# epm_control.net
KiCad netlist of a schematic drawn in Altium Designer
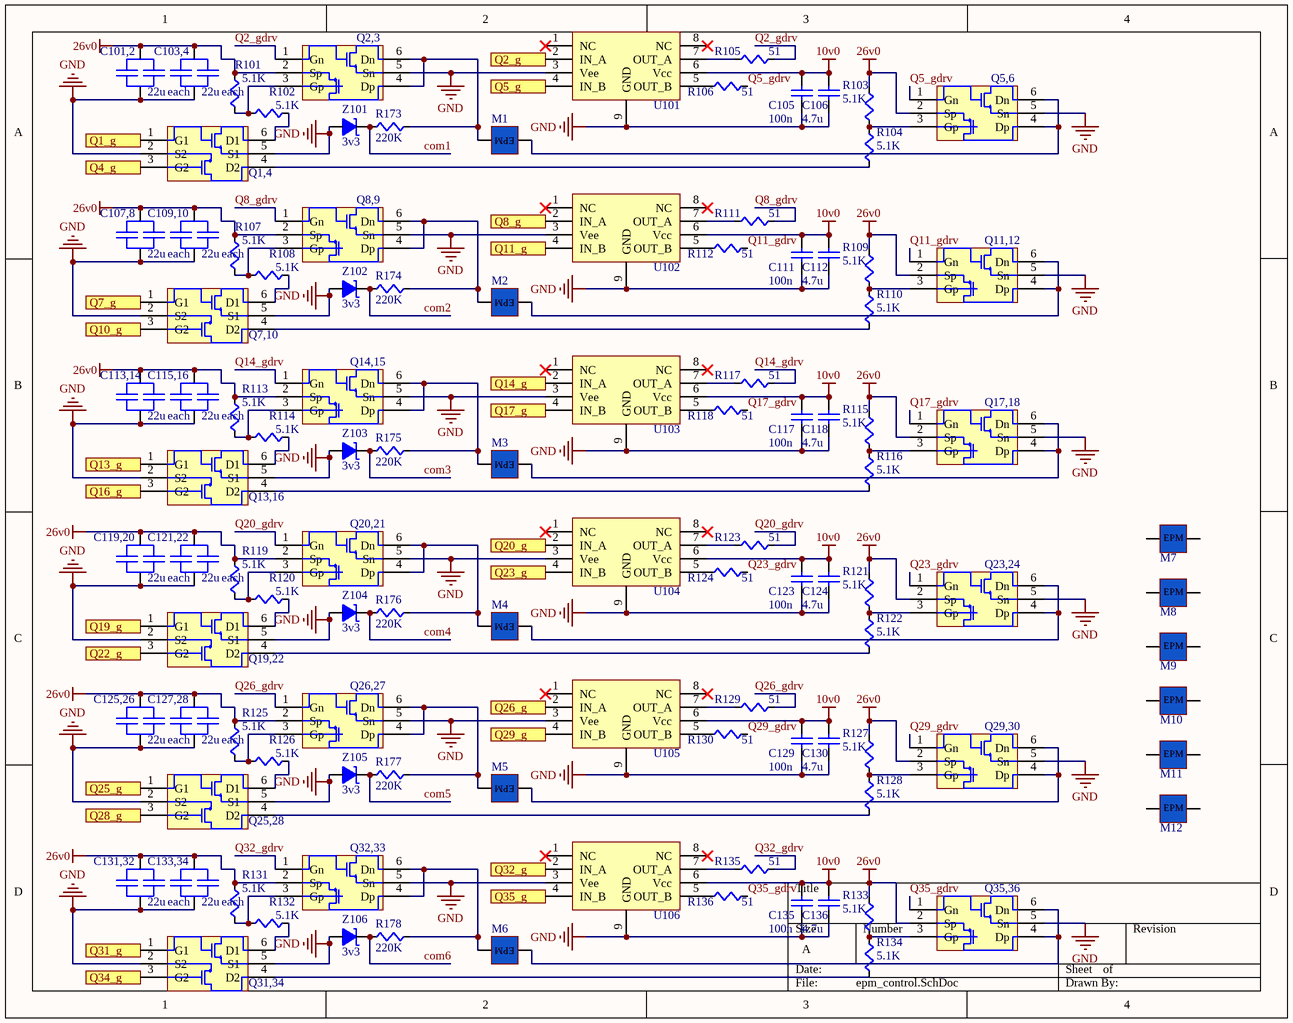
[diagram p0: epm_control.SchDoc]

(export (version "E")
  (design (tool "Eeschema 10.0.6"))
  (components
    (comp (ref "C101,2")
      (value "22u")
      (footprint "dicap_smd_1206")
      (fields (field (name "Comment") "Dicap"))
      (libsource (lib "Components") (part "Dicap"))
    )
    (comp (ref "C103,4")
      (value "22u")
      (footprint "dicap_smd_1206")
      (fields (field (name "Comment") "Dicap"))
      (libsource (lib "Components") (part "Dicap"))
    )
    (comp (ref "C105")
      (value "100n")
      (footprint "SMD0603_cap")
      (description "Ceramic Chip Capacitor")
      (fields (field (name "Comment") "Cap"))
      (libsource (lib "Components") (part "Capacitor Ceramic"))
    )
    (comp (ref "C106")
      (value "4.7u")
      (footprint "SMD0603_cap")
      (description "Ceramic Chip Capacitor")
      (fields (field (name "Comment") "Cap"))
      (libsource (lib "Components") (part "Capacitor Ceramic"))
    )
    (comp (ref "C107,8")
      (value "22u")
      (footprint "dicap_smd_1206")
      (fields (field (name "Comment") "Dicap"))
      (libsource (lib "Components") (part "Dicap"))
    )
    (comp (ref "C109,10")
      (value "22u")
      (footprint "dicap_smd_1206")
      (fields (field (name "Comment") "Dicap"))
      (libsource (lib "Components") (part "Dicap"))
    )
    (comp (ref "C111")
      (value "100n")
      (footprint "SMD0603_cap")
      (description "Ceramic Chip Capacitor")
      (fields (field (name "Comment") "Cap"))
      (libsource (lib "Components") (part "Capacitor Ceramic"))
    )
    (comp (ref "C112")
      (value "4.7u")
      (footprint "SMD0603_cap")
      (description "Ceramic Chip Capacitor")
      (fields (field (name "Comment") "Cap"))
      (libsource (lib "Components") (part "Capacitor Ceramic"))
    )
    (comp (ref "C113,14")
      (value "22u")
      (footprint "dicap_smd_1206")
      (fields (field (name "Comment") "Dicap"))
      (libsource (lib "Components") (part "Dicap"))
    )
    (comp (ref "C115,16")
      (value "22u")
      (footprint "dicap_smd_1206")
      (fields (field (name "Comment") "Dicap"))
      (libsource (lib "Components") (part "Dicap"))
    )
    (comp (ref "C117")
      (value "100n")
      (footprint "SMD0603_cap")
      (description "Ceramic Chip Capacitor")
      (fields (field (name "Comment") "Cap"))
      (libsource (lib "Components") (part "Capacitor Ceramic"))
    )
    (comp (ref "C118")
      (value "4.7u")
      (footprint "SMD0603_cap")
      (description "Ceramic Chip Capacitor")
      (fields (field (name "Comment") "Cap"))
      (libsource (lib "Components") (part "Capacitor Ceramic"))
    )
    (comp (ref "C119,20")
      (value "22u")
      (footprint "dicap_smd_1206")
      (fields (field (name "Comment") "Dicap"))
      (libsource (lib "Components") (part "Dicap"))
    )
    (comp (ref "C121,22")
      (value "22u")
      (footprint "dicap_smd_1206")
      (fields (field (name "Comment") "Dicap"))
      (libsource (lib "Components") (part "Dicap"))
    )
    (comp (ref "C123")
      (value "100n")
      (footprint "SMD0603_cap")
      (description "Ceramic Chip Capacitor")
      (fields (field (name "Comment") "Cap"))
      (libsource (lib "Components") (part "Capacitor Ceramic"))
    )
    (comp (ref "C124")
      (value "4.7u")
      (footprint "SMD0603_cap")
      (description "Ceramic Chip Capacitor")
      (fields (field (name "Comment") "Cap"))
      (libsource (lib "Components") (part "Capacitor Ceramic"))
    )
    (comp (ref "C125,26")
      (value "22u")
      (footprint "dicap_smd_1206")
      (fields (field (name "Comment") "Dicap"))
      (libsource (lib "Components") (part "Dicap"))
    )
    (comp (ref "C127,28")
      (value "22u")
      (footprint "dicap_smd_1206")
      (fields (field (name "Comment") "Dicap"))
      (libsource (lib "Components") (part "Dicap"))
    )
    (comp (ref "C129")
      (value "100n")
      (footprint "SMD0603_cap")
      (description "Ceramic Chip Capacitor")
      (fields (field (name "Comment") "Cap"))
      (libsource (lib "Components") (part "Capacitor Ceramic"))
    )
    (comp (ref "C130")
      (value "4.7u")
      (footprint "SMD0603_cap")
      (description "Ceramic Chip Capacitor")
      (fields (field (name "Comment") "Cap"))
      (libsource (lib "Components") (part "Capacitor Ceramic"))
    )
    (comp (ref "C131,32")
      (value "22u")
      (footprint "dicap_smd_1206")
      (fields (field (name "Comment") "Dicap"))
      (libsource (lib "Components") (part "Dicap"))
    )
    (comp (ref "C133,34")
      (value "22u")
      (footprint "dicap_smd_1206")
      (fields (field (name "Comment") "Dicap"))
      (libsource (lib "Components") (part "Dicap"))
    )
    (comp (ref "C135")
      (value "100n")
      (footprint "SMD0603_cap")
      (description "Ceramic Chip Capacitor")
      (fields (field (name "Comment") "Cap"))
      (libsource (lib "Components") (part "Capacitor Ceramic"))
    )
    (comp (ref "C136")
      (value "4.7u")
      (footprint "SMD0603_cap")
      (description "Ceramic Chip Capacitor")
      (fields (field (name "Comment") "Cap"))
      (libsource (lib "Components") (part "Capacitor Ceramic"))
    )
    (comp (ref "M1") (value "EPM") (footprint "40awg_epm") (libsource (lib "Components") (part "EPM")))
    (comp (ref "M2") (value "EPM") (footprint "40awg_epm") (libsource (lib "Components") (part "EPM")))
    (comp (ref "M3") (value "EPM") (footprint "40awg_epm") (libsource (lib "Components") (part "EPM")))
    (comp (ref "M4") (value "EPM") (footprint "40awg_epm") (libsource (lib "Components") (part "EPM")))
    (comp (ref "M5") (value "EPM") (footprint "40awg_epm") (libsource (lib "Components") (part "EPM")))
    (comp (ref "M6") (value "EPM") (footprint "40awg_epm") (libsource (lib "Components") (part "EPM")))
    (comp (ref "M7") (value "EPM") (footprint "40awg_epm") (libsource (lib "") (part "EPM_1")))
    (comp (ref "M8") (value "EPM") (footprint "40awg_epm") (libsource (lib "") (part "EPM_1")))
    (comp (ref "M9") (value "EPM") (footprint "40awg_epm") (libsource (lib "") (part "EPM_1")))
    (comp (ref "M10") (value "EPM") (footprint "40awg_epm") (libsource (lib "") (part "EPM_1")))
    (comp (ref "M11") (value "EPM") (footprint "40awg_epm") (libsource (lib "") (part "EPM_1")))
    (comp (ref "M12") (value "EPM") (footprint "40awg_epm") (libsource (lib "") (part "EPM_1")))
    (comp (ref "Q1,4") (value "SI3292") (footprint "sot23-6l") (libsource (lib "Components") (part "SI3292")))
    (comp (ref "Q2,3")
      (value "DMG6602")
      (footprint "sot23-6l")
      (libsource (lib "Components") (part "DMG6602"))
    )
    (comp (ref "Q5,6")
      (value "DMG6602")
      (footprint "sot23-6l")
      (libsource (lib "Components") (part "DMG6602"))
    )
    (comp (ref "Q7,10")
      (value "SI3292")
      (footprint "sot23-6l")
      (libsource (lib "Components") (part "SI3292"))
    )
    (comp (ref "Q8,9")
      (value "DMG6602")
      (footprint "sot23-6l")
      (libsource (lib "Components") (part "DMG6602"))
    )
    (comp (ref "Q11,12")
      (value "DMG6602")
      (footprint "sot23-6l")
      (libsource (lib "Components") (part "DMG6602"))
    )
    (comp (ref "Q13,16")
      (value "SI3292")
      (footprint "sot23-6l")
      (libsource (lib "Components") (part "SI3292"))
    )
    (comp (ref "Q14,15")
      (value "DMG6602")
      (footprint "sot23-6l")
      (libsource (lib "Components") (part "DMG6602"))
    )
    (comp (ref "Q17,18")
      (value "DMG6602")
      (footprint "sot23-6l")
      (libsource (lib "Components") (part "DMG6602"))
    )
    (comp (ref "Q19,22")
      (value "SI3292")
      (footprint "sot23-6l")
      (libsource (lib "Components") (part "SI3292"))
    )
    (comp (ref "Q20,21")
      (value "DMG6602")
      (footprint "sot23-6l")
      (libsource (lib "Components") (part "DMG6602"))
    )
    (comp (ref "Q23,24")
      (value "DMG6602")
      (footprint "sot23-6l")
      (libsource (lib "Components") (part "DMG6602"))
    )
    (comp (ref "Q25,28")
      (value "SI3292")
      (footprint "sot23-6l")
      (libsource (lib "Components") (part "SI3292"))
    )
    (comp (ref "Q26,27")
      (value "DMG6602")
      (footprint "sot23-6l")
      (libsource (lib "Components") (part "DMG6602"))
    )
    (comp (ref "Q29,30")
      (value "DMG6602")
      (footprint "sot23-6l")
      (libsource (lib "Components") (part "DMG6602"))
    )
    (comp (ref "Q31,34")
      (value "SI3292")
      (footprint "sot23-6l")
      (libsource (lib "Components") (part "SI3292"))
    )
    (comp (ref "Q32,33")
      (value "DMG6602")
      (footprint "sot23-6l")
      (libsource (lib "Components") (part "DMG6602"))
    )
    (comp (ref "Q35,36")
      (value "DMG6602")
      (footprint "sot23-6l")
      (libsource (lib "Components") (part "DMG6602"))
    )
    (comp (ref "R101")
      (value "5.1K")
      (footprint "SMD0603")
      (description "Resistor")
      (fields (field (name "Comment") "Res"))
      (libsource (lib "Components") (part "Resistor"))
    )
    (comp (ref "R102")
      (value "5.1K")
      (footprint "SMD0603")
      (description "Resistor")
      (fields (field (name "Comment") "Res"))
      (libsource (lib "Components") (part "Resistor"))
    )
    (comp (ref "R103")
      (value "5.1K")
      (footprint "SMD0603")
      (description "Resistor")
      (fields (field (name "Comment") "Res"))
      (libsource (lib "Components") (part "Resistor"))
    )
    (comp (ref "R104")
      (value "5.1K")
      (footprint "SMD0603")
      (description "Resistor")
      (fields (field (name "Comment") "Res"))
      (libsource (lib "Components") (part "Resistor"))
    )
    (comp (ref "R105")
      (value "51")
      (footprint "SMD0603")
      (description "Resistor")
      (fields (field (name "Comment") "Res"))
      (libsource (lib "Components") (part "Resistor"))
    )
    (comp (ref "R106")
      (value "51")
      (footprint "SMD0603")
      (description "Resistor")
      (fields (field (name "Comment") "Res"))
      (libsource (lib "Components") (part "Resistor"))
    )
    (comp (ref "R107")
      (value "5.1K")
      (footprint "SMD0603")
      (description "Resistor")
      (fields (field (name "Comment") "Res"))
      (libsource (lib "Components") (part "Resistor"))
    )
    (comp (ref "R108")
      (value "5.1K")
      (footprint "SMD0603")
      (description "Resistor")
      (fields (field (name "Comment") "Res"))
      (libsource (lib "Components") (part "Resistor"))
    )
    (comp (ref "R109")
      (value "5.1K")
      (footprint "SMD0603")
      (description "Resistor")
      (fields (field (name "Comment") "Res"))
      (libsource (lib "Components") (part "Resistor"))
    )
    (comp (ref "R110")
      (value "5.1K")
      (footprint "SMD0603")
      (description "Resistor")
      (fields (field (name "Comment") "Res"))
      (libsource (lib "Components") (part "Resistor"))
    )
    (comp (ref "R111")
      (value "51")
      (footprint "SMD0603")
      (description "Resistor")
      (fields (field (name "Comment") "Res"))
      (libsource (lib "Components") (part "Resistor"))
    )
    (comp (ref "R112")
      (value "51")
      (footprint "SMD0603")
      (description "Resistor")
      (fields (field (name "Comment") "Res"))
      (libsource (lib "Components") (part "Resistor"))
    )
    (comp (ref "R113")
      (value "5.1K")
      (footprint "SMD0603")
      (description "Resistor")
      (fields (field (name "Comment") "Res"))
      (libsource (lib "Components") (part "Resistor"))
    )
    (comp (ref "R114")
      (value "5.1K")
      (footprint "SMD0603")
      (description "Resistor")
      (fields (field (name "Comment") "Res"))
      (libsource (lib "Components") (part "Resistor"))
    )
    (comp (ref "R115")
      (value "5.1K")
      (footprint "SMD0603")
      (description "Resistor")
      (fields (field (name "Comment") "Res"))
      (libsource (lib "Components") (part "Resistor"))
    )
    (comp (ref "R116")
      (value "5.1K")
      (footprint "SMD0603")
      (description "Resistor")
      (fields (field (name "Comment") "Res"))
      (libsource (lib "Components") (part "Resistor"))
    )
    (comp (ref "R117")
      (value "51")
      (footprint "SMD0603")
      (description "Resistor")
      (fields (field (name "Comment") "Res"))
      (libsource (lib "Components") (part "Resistor"))
    )
    (comp (ref "R118")
      (value "51")
      (footprint "SMD0603")
      (description "Resistor")
      (fields (field (name "Comment") "Res"))
      (libsource (lib "Components") (part "Resistor"))
    )
    (comp (ref "R119")
      (value "5.1K")
      (footprint "SMD0603")
      (description "Resistor")
      (fields (field (name "Comment") "Res"))
      (libsource (lib "Components") (part "Resistor"))
    )
    (comp (ref "R120")
      (value "5.1K")
      (footprint "SMD0603")
      (description "Resistor")
      (fields (field (name "Comment") "Res"))
      (libsource (lib "Components") (part "Resistor"))
    )
    (comp (ref "R121")
      (value "5.1K")
      (footprint "SMD0603")
      (description "Resistor")
      (fields (field (name "Comment") "Res"))
      (libsource (lib "Components") (part "Resistor"))
    )
    (comp (ref "R122")
      (value "5.1K")
      (footprint "SMD0603")
      (description "Resistor")
      (fields (field (name "Comment") "Res"))
      (libsource (lib "Components") (part "Resistor"))
    )
    (comp (ref "R123")
      (value "51")
      (footprint "SMD0603")
      (description "Resistor")
      (fields (field (name "Comment") "Res"))
      (libsource (lib "Components") (part "Resistor"))
    )
    (comp (ref "R124")
      (value "51")
      (footprint "SMD0603")
      (description "Resistor")
      (fields (field (name "Comment") "Res"))
      (libsource (lib "Components") (part "Resistor"))
    )
    (comp (ref "R125")
      (value "5.1K")
      (footprint "SMD0603")
      (description "Resistor")
      (fields (field (name "Comment") "Res"))
      (libsource (lib "Components") (part "Resistor"))
    )
    (comp (ref "R126")
      (value "5.1K")
      (footprint "SMD0603")
      (description "Resistor")
      (fields (field (name "Comment") "Res"))
      (libsource (lib "Components") (part "Resistor"))
    )
    (comp (ref "R127")
      (value "5.1K")
      (footprint "SMD0603")
      (description "Resistor")
      (fields (field (name "Comment") "Res"))
      (libsource (lib "Components") (part "Resistor"))
    )
    (comp (ref "R128")
      (value "5.1K")
      (footprint "SMD0603")
      (description "Resistor")
      (fields (field (name "Comment") "Res"))
      (libsource (lib "Components") (part "Resistor"))
    )
    (comp (ref "R129")
      (value "51")
      (footprint "SMD0603")
      (description "Resistor")
      (fields (field (name "Comment") "Res"))
      (libsource (lib "Components") (part "Resistor"))
    )
    (comp (ref "R130")
      (value "51")
      (footprint "SMD0603")
      (description "Resistor")
      (fields (field (name "Comment") "Res"))
      (libsource (lib "Components") (part "Resistor"))
    )
    (comp (ref "R131")
      (value "5.1K")
      (footprint "SMD0603")
      (description "Resistor")
      (fields (field (name "Comment") "Res"))
      (libsource (lib "Components") (part "Resistor"))
    )
    (comp (ref "R132")
      (value "5.1K")
      (footprint "SMD0603")
      (description "Resistor")
      (fields (field (name "Comment") "Res"))
      (libsource (lib "Components") (part "Resistor"))
    )
    (comp (ref "R133")
      (value "5.1K")
      (footprint "SMD0603")
      (description "Resistor")
      (fields (field (name "Comment") "Res"))
      (libsource (lib "Components") (part "Resistor"))
    )
    (comp (ref "R134")
      (value "5.1K")
      (footprint "SMD0603")
      (description "Resistor")
      (fields (field (name "Comment") "Res"))
      (libsource (lib "Components") (part "Resistor"))
    )
    (comp (ref "R135")
      (value "51")
      (footprint "SMD0603")
      (description "Resistor")
      (fields (field (name "Comment") "Res"))
      (libsource (lib "Components") (part "Resistor"))
    )
    (comp (ref "R136")
      (value "51")
      (footprint "SMD0603")
      (description "Resistor")
      (fields (field (name "Comment") "Res"))
      (libsource (lib "Components") (part "Resistor"))
    )
    (comp (ref "R173")
      (value "220K")
      (footprint "SMD0603")
      (description "Resistor")
      (fields (field (name "Comment") "Res"))
      (libsource (lib "Components") (part "Resistor"))
    )
    (comp (ref "R174")
      (value "220K")
      (footprint "SMD0603")
      (description "Resistor")
      (fields (field (name "Comment") "Res"))
      (libsource (lib "Components") (part "Resistor"))
    )
    (comp (ref "R175")
      (value "220K")
      (footprint "SMD0603")
      (description "Resistor")
      (fields (field (name "Comment") "Res"))
      (libsource (lib "Components") (part "Resistor"))
    )
    (comp (ref "R176")
      (value "220K")
      (footprint "SMD0603")
      (description "Resistor")
      (fields (field (name "Comment") "Res"))
      (libsource (lib "Components") (part "Resistor"))
    )
    (comp (ref "R177")
      (value "220K")
      (footprint "SMD0603")
      (description "Resistor")
      (fields (field (name "Comment") "Res"))
      (libsource (lib "Components") (part "Resistor"))
    )
    (comp (ref "R178")
      (value "220K")
      (footprint "SMD0603")
      (description "Resistor")
      (fields (field (name "Comment") "Res"))
      (libsource (lib "Components") (part "Resistor"))
    )
    (comp (ref "U101")
      (value "LM5111-1")
      (footprint "tssop-8")
      (libsource (lib "Components") (part "LM5111-1"))
    )
    (comp (ref "U102")
      (value "LM5111-1")
      (footprint "tssop-8")
      (libsource (lib "Components") (part "LM5111-1"))
    )
    (comp (ref "U103")
      (value "LM5111-1")
      (footprint "tssop-8")
      (libsource (lib "Components") (part "LM5111-1"))
    )
    (comp (ref "U104")
      (value "LM5111-1")
      (footprint "tssop-8")
      (libsource (lib "Components") (part "LM5111-1"))
    )
    (comp (ref "U105")
      (value "LM5111-1")
      (footprint "tssop-8")
      (libsource (lib "Components") (part "LM5111-1"))
    )
    (comp (ref "U106")
      (value "LM5111-1")
      (footprint "tssop-8")
      (libsource (lib "Components") (part "LM5111-1"))
    )
    (comp (ref "Z101")
      (value "3v3")
      (footprint "SOD-323F")
      (fields (field (name "Comment") "Zener"))
      (libsource (lib "Components") (part "Zener"))
    )
    (comp (ref "Z102")
      (value "3v3")
      (footprint "SOD-323F")
      (fields (field (name "Comment") "Zener"))
      (libsource (lib "Components") (part "Zener"))
    )
    (comp (ref "Z103")
      (value "3v3")
      (footprint "SOD-323F")
      (fields (field (name "Comment") "Zener"))
      (libsource (lib "Components") (part "Zener"))
    )
    (comp (ref "Z104")
      (value "3v3")
      (footprint "SOD-323F")
      (fields (field (name "Comment") "Zener"))
      (libsource (lib "Components") (part "Zener"))
    )
    (comp (ref "Z105")
      (value "3v3")
      (footprint "SOD-323F")
      (fields (field (name "Comment") "Zener"))
      (libsource (lib "Components") (part "Zener"))
    )
    (comp (ref "Z106")
      (value "3v3")
      (footprint "SOD-323F")
      (fields (field (name "Comment") "Zener"))
      (libsource (lib "Components") (part "Zener"))
    )
  )
  (nets
    (net (code "1") (name "/Q1_g") (class "Default")
      (node (ref "Q1,4") (pin "1") (pinfunction "G1_1") (pintype "passive"))
    )
    (net (code "2") (name "/Q2_g") (class "Default")
      (node (ref "U101") (pin "2") (pinfunction "IN_A_2") (pintype "passive"))
    )
    (net (code "3") (name "/Q2_gdrv") (class "Default")
      (node (ref "Q2,3") (pin "1") (pinfunction "Gn_1") (pintype "passive"))
      (node (ref "R105") (pin "1") (pinfunction "1_1") (pintype "passive"))
    )
    (net (code "4") (name "/Q4_g") (class "Default")
      (node (ref "Q1,4") (pin "3") (pinfunction "G2_3") (pintype "passive"))
    )
    (net (code "5") (name "/Q5_g") (class "Default")
      (node (ref "U101") (pin "4") (pinfunction "IN_B_4") (pintype "passive"))
    )
    (net (code "6") (name "/Q5_gdrv") (class "Default")
      (node (ref "Q5,6") (pin "1") (pinfunction "Gn_1") (pintype "passive"))
      (node (ref "R106") (pin "1") (pinfunction "1_1") (pintype "passive"))
    )
    (net (code "7") (name "/Q7_g") (class "Default")
      (node (ref "Q7,10") (pin "1") (pinfunction "G1_1") (pintype "passive"))
    )
    (net (code "8") (name "/Q8_g") (class "Default")
      (node (ref "U102") (pin "2") (pinfunction "IN_A_2") (pintype "passive"))
    )
    (net (code "9") (name "/Q8_gdrv") (class "Default")
      (node (ref "Q8,9") (pin "1") (pinfunction "Gn_1") (pintype "passive"))
      (node (ref "R111") (pin "1") (pinfunction "1_1") (pintype "passive"))
    )
    (net (code "10") (name "/Q10_g") (class "Default")
      (node (ref "Q7,10") (pin "3") (pinfunction "G2_3") (pintype "passive"))
    )
    (net (code "11") (name "/Q11_g") (class "Default")
      (node (ref "U102") (pin "4") (pinfunction "IN_B_4") (pintype "passive"))
    )
    (net (code "12") (name "/Q11_gdrv") (class "Default")
      (node (ref "Q11,12") (pin "1") (pinfunction "Gn_1") (pintype "passive"))
      (node (ref "R112") (pin "1") (pinfunction "1_1") (pintype "passive"))
    )
    (net (code "13") (name "/Q13_g") (class "Default")
      (node (ref "Q13,16") (pin "1") (pinfunction "G1_1") (pintype "passive"))
    )
    (net (code "14") (name "/Q14_g") (class "Default")
      (node (ref "U103") (pin "2") (pinfunction "IN_A_2") (pintype "passive"))
    )
    (net (code "15") (name "/Q14_gdrv") (class "Default")
      (node (ref "Q14,15") (pin "1") (pinfunction "Gn_1") (pintype "passive"))
      (node (ref "R117") (pin "1") (pinfunction "1_1") (pintype "passive"))
    )
    (net (code "16") (name "/Q16_g") (class "Default")
      (node (ref "Q13,16") (pin "3") (pinfunction "G2_3") (pintype "passive"))
    )
    (net (code "17") (name "/Q17_g") (class "Default")
      (node (ref "U103") (pin "4") (pinfunction "IN_B_4") (pintype "passive"))
    )
    (net (code "18") (name "/Q17_gdrv") (class "Default")
      (node (ref "Q17,18") (pin "1") (pinfunction "Gn_1") (pintype "passive"))
      (node (ref "R118") (pin "1") (pinfunction "1_1") (pintype "passive"))
    )
    (net (code "19") (name "/Q19_g") (class "Default")
      (node (ref "Q19,22") (pin "1") (pinfunction "G1_1") (pintype "passive"))
    )
    (net (code "20") (name "/Q20_g") (class "Default")
      (node (ref "U104") (pin "2") (pinfunction "IN_A_2") (pintype "passive"))
    )
    (net (code "21") (name "/Q20_gdrv") (class "Default")
      (node (ref "Q20,21") (pin "1") (pinfunction "Gn_1") (pintype "passive"))
      (node (ref "R123") (pin "1") (pinfunction "1_1") (pintype "passive"))
    )
    (net (code "22") (name "/Q22_g") (class "Default")
      (node (ref "Q19,22") (pin "3") (pinfunction "G2_3") (pintype "passive"))
    )
    (net (code "23") (name "/Q23_g") (class "Default")
      (node (ref "U104") (pin "4") (pinfunction "IN_B_4") (pintype "passive"))
    )
    (net (code "24") (name "/Q23_gdrv") (class "Default")
      (node (ref "Q23,24") (pin "1") (pinfunction "Gn_1") (pintype "passive"))
      (node (ref "R124") (pin "1") (pinfunction "1_1") (pintype "passive"))
    )
    (net (code "25") (name "/Q25_g") (class "Default")
      (node (ref "Q25,28") (pin "1") (pinfunction "G1_1") (pintype "passive"))
    )
    (net (code "26") (name "/Q26_g") (class "Default")
      (node (ref "U105") (pin "2") (pinfunction "IN_A_2") (pintype "passive"))
    )
    (net (code "27") (name "/Q26_gdrv") (class "Default")
      (node (ref "Q26,27") (pin "1") (pinfunction "Gn_1") (pintype "passive"))
      (node (ref "R129") (pin "1") (pinfunction "1_1") (pintype "passive"))
    )
    (net (code "28") (name "/Q28_g") (class "Default")
      (node (ref "Q25,28") (pin "3") (pinfunction "G2_3") (pintype "passive"))
    )
    (net (code "29") (name "/Q29_g") (class "Default")
      (node (ref "U105") (pin "4") (pinfunction "IN_B_4") (pintype "passive"))
    )
    (net (code "30") (name "/Q29_gdrv") (class "Default")
      (node (ref "Q29,30") (pin "1") (pinfunction "Gn_1") (pintype "passive"))
      (node (ref "R130") (pin "1") (pinfunction "1_1") (pintype "passive"))
    )
    (net (code "31") (name "/Q31_g") (class "Default")
      (node (ref "Q31,34") (pin "1") (pinfunction "G1_1") (pintype "passive"))
    )
    (net (code "32") (name "/Q32_g") (class "Default")
      (node (ref "U106") (pin "2") (pinfunction "IN_A_2") (pintype "passive"))
    )
    (net (code "33") (name "/Q32_gdrv") (class "Default")
      (node (ref "Q32,33") (pin "1") (pinfunction "Gn_1") (pintype "passive"))
      (node (ref "R135") (pin "1") (pinfunction "1_1") (pintype "passive"))
    )
    (net (code "34") (name "/Q34_g") (class "Default")
      (node (ref "Q31,34") (pin "3") (pinfunction "G2_3") (pintype "passive"))
    )
    (net (code "35") (name "/Q35_g") (class "Default")
      (node (ref "U106") (pin "4") (pinfunction "IN_B_4") (pintype "passive"))
    )
    (net (code "36") (name "/Q35_gdrv") (class "Default")
      (node (ref "Q35,36") (pin "1") (pinfunction "Gn_1") (pintype "passive"))
      (node (ref "R136") (pin "1") (pinfunction "1_1") (pintype "passive"))
    )
    (net (code "37") (name "/com1") (class "Default")
      (node (ref "R173") (pin "1") (pinfunction "1_1") (pintype "passive"))
      (node (ref "Z101") (pin "K") (pinfunction "2_K") (pintype "passive"))
    )
    (net (code "38") (name "/com2") (class "Default")
      (node (ref "R174") (pin "1") (pinfunction "1_1") (pintype "passive"))
      (node (ref "Z102") (pin "K") (pinfunction "2_K") (pintype "passive"))
    )
    (net (code "39") (name "/com3") (class "Default")
      (node (ref "R175") (pin "1") (pinfunction "1_1") (pintype "passive"))
      (node (ref "Z103") (pin "K") (pinfunction "2_K") (pintype "passive"))
    )
    (net (code "40") (name "/com4") (class "Default")
      (node (ref "R176") (pin "1") (pinfunction "1_1") (pintype "passive"))
      (node (ref "Z104") (pin "K") (pinfunction "2_K") (pintype "passive"))
    )
    (net (code "41") (name "/com5") (class "Default")
      (node (ref "R177") (pin "1") (pinfunction "1_1") (pintype "passive"))
      (node (ref "Z105") (pin "K") (pinfunction "2_K") (pintype "passive"))
    )
    (net (code "42") (name "/com6") (class "Default")
      (node (ref "R178") (pin "1") (pinfunction "1_1") (pintype "passive"))
      (node (ref "Z106") (pin "K") (pinfunction "2_K") (pintype "passive"))
    )
    (net (code "43") (name "10v0") (class "Default")
      (node (ref "C105") (pin "2") (pinfunction "2_2") (pintype "passive"))
      (node (ref "C106") (pin "2") (pinfunction "2_2") (pintype "passive"))
      (node (ref "C111") (pin "2") (pinfunction "2_2") (pintype "passive"))
      (node (ref "C112") (pin "2") (pinfunction "2_2") (pintype "passive"))
      (node (ref "C117") (pin "2") (pinfunction "2_2") (pintype "passive"))
      (node (ref "C118") (pin "2") (pinfunction "2_2") (pintype "passive"))
      (node (ref "C123") (pin "2") (pinfunction "2_2") (pintype "passive"))
      (node (ref "C124") (pin "2") (pinfunction "2_2") (pintype "passive"))
      (node (ref "C129") (pin "2") (pinfunction "2_2") (pintype "passive"))
      (node (ref "C130") (pin "2") (pinfunction "2_2") (pintype "passive"))
      (node (ref "C135") (pin "2") (pinfunction "2_2") (pintype "passive"))
      (node (ref "C136") (pin "2") (pinfunction "2_2") (pintype "passive"))
      (node (ref "U101") (pin "6") (pinfunction "Vcc_6") (pintype "passive"))
      (node (ref "U102") (pin "6") (pinfunction "Vcc_6") (pintype "passive"))
      (node (ref "U103") (pin "6") (pinfunction "Vcc_6") (pintype "passive"))
      (node (ref "U104") (pin "6") (pinfunction "Vcc_6") (pintype "passive"))
      (node (ref "U105") (pin "6") (pinfunction "Vcc_6") (pintype "passive"))
      (node (ref "U106") (pin "6") (pinfunction "Vcc_6") (pintype "passive"))
    )
    (net (code "44") (name "26v0") (class "Default")
      (node (ref "C101,2") (pin "2") (pinfunction "2_2") (pintype "passive"))
      (node (ref "C103,4") (pin "2") (pinfunction "2_2") (pintype "passive"))
      (node (ref "C107,8") (pin "2") (pinfunction "2_2") (pintype "passive"))
      (node (ref "C109,10") (pin "2") (pinfunction "2_2") (pintype "passive"))
      (node (ref "C113,14") (pin "2") (pinfunction "2_2") (pintype "passive"))
      (node (ref "C115,16") (pin "2") (pinfunction "2_2") (pintype "passive"))
      (node (ref "C119,20") (pin "2") (pinfunction "2_2") (pintype "passive"))
      (node (ref "C121,22") (pin "2") (pinfunction "2_2") (pintype "passive"))
      (node (ref "C125,26") (pin "2") (pinfunction "2_2") (pintype "passive"))
      (node (ref "C127,28") (pin "2") (pinfunction "2_2") (pintype "passive"))
      (node (ref "C131,32") (pin "2") (pinfunction "2_2") (pintype "passive"))
      (node (ref "C133,34") (pin "2") (pinfunction "2_2") (pintype "passive"))
      (node (ref "Q11,12") (pin "2") (pinfunction "Sp_2") (pintype "passive"))
      (node (ref "Q14,15") (pin "2") (pinfunction "Sp_2") (pintype "passive"))
      (node (ref "Q17,18") (pin "2") (pinfunction "Sp_2") (pintype "passive"))
      (node (ref "Q2,3") (pin "2") (pinfunction "Sp_2") (pintype "passive"))
      (node (ref "Q20,21") (pin "2") (pinfunction "Sp_2") (pintype "passive"))
      (node (ref "Q23,24") (pin "2") (pinfunction "Sp_2") (pintype "passive"))
      (node (ref "Q26,27") (pin "2") (pinfunction "Sp_2") (pintype "passive"))
      (node (ref "Q29,30") (pin "2") (pinfunction "Sp_2") (pintype "passive"))
      (node (ref "Q32,33") (pin "2") (pinfunction "Sp_2") (pintype "passive"))
      (node (ref "Q35,36") (pin "2") (pinfunction "Sp_2") (pintype "passive"))
      (node (ref "Q5,6") (pin "2") (pinfunction "Sp_2") (pintype "passive"))
      (node (ref "Q8,9") (pin "2") (pinfunction "Sp_2") (pintype "passive"))
      (node (ref "R101") (pin "2") (pinfunction "2_2") (pintype "passive"))
      (node (ref "R103") (pin "2") (pinfunction "2_2") (pintype "passive"))
      (node (ref "R107") (pin "2") (pinfunction "2_2") (pintype "passive"))
      (node (ref "R109") (pin "2") (pinfunction "2_2") (pintype "passive"))
      (node (ref "R113") (pin "2") (pinfunction "2_2") (pintype "passive"))
      (node (ref "R115") (pin "2") (pinfunction "2_2") (pintype "passive"))
      (node (ref "R119") (pin "2") (pinfunction "2_2") (pintype "passive"))
      (node (ref "R121") (pin "2") (pinfunction "2_2") (pintype "passive"))
      (node (ref "R125") (pin "2") (pinfunction "2_2") (pintype "passive"))
      (node (ref "R127") (pin "2") (pinfunction "2_2") (pintype "passive"))
      (node (ref "R131") (pin "2") (pinfunction "2_2") (pintype "passive"))
      (node (ref "R133") (pin "2") (pinfunction "2_2") (pintype "passive"))
    )
    (net (code "45") (name "GND") (class "Default")
      (node (ref "C101,2") (pin "1") (pinfunction "1_1") (pintype "passive"))
      (node (ref "C103,4") (pin "1") (pinfunction "1_1") (pintype "passive"))
      (node (ref "C105") (pin "1") (pinfunction "1_1") (pintype "passive"))
      (node (ref "C106") (pin "1") (pinfunction "1_1") (pintype "passive"))
      (node (ref "C107,8") (pin "1") (pinfunction "1_1") (pintype "passive"))
      (node (ref "C109,10") (pin "1") (pinfunction "1_1") (pintype "passive"))
      (node (ref "C111") (pin "1") (pinfunction "1_1") (pintype "passive"))
      (node (ref "C112") (pin "1") (pinfunction "1_1") (pintype "passive"))
      (node (ref "C113,14") (pin "1") (pinfunction "1_1") (pintype "passive"))
      (node (ref "C115,16") (pin "1") (pinfunction "1_1") (pintype "passive"))
      (node (ref "C117") (pin "1") (pinfunction "1_1") (pintype "passive"))
      (node (ref "C118") (pin "1") (pinfunction "1_1") (pintype "passive"))
      (node (ref "C119,20") (pin "1") (pinfunction "1_1") (pintype "passive"))
      (node (ref "C121,22") (pin "1") (pinfunction "1_1") (pintype "passive"))
      (node (ref "C123") (pin "1") (pinfunction "1_1") (pintype "passive"))
      (node (ref "C124") (pin "1") (pinfunction "1_1") (pintype "passive"))
      (node (ref "C125,26") (pin "1") (pinfunction "1_1") (pintype "passive"))
      (node (ref "C127,28") (pin "1") (pinfunction "1_1") (pintype "passive"))
      (node (ref "C129") (pin "1") (pinfunction "1_1") (pintype "passive"))
      (node (ref "C130") (pin "1") (pinfunction "1_1") (pintype "passive"))
      (node (ref "C131,32") (pin "1") (pinfunction "1_1") (pintype "passive"))
      (node (ref "C133,34") (pin "1") (pinfunction "1_1") (pintype "passive"))
      (node (ref "C135") (pin "1") (pinfunction "1_1") (pintype "passive"))
      (node (ref "C136") (pin "1") (pinfunction "1_1") (pintype "passive"))
      (node (ref "Q1,4") (pin "2") (pinfunction "S2_2") (pintype "passive"))
      (node (ref "Q1,4") (pin "5") (pinfunction "S1_5") (pintype "passive"))
      (node (ref "Q11,12") (pin "5") (pinfunction "Sn_5") (pintype "passive"))
      (node (ref "Q13,16") (pin "2") (pinfunction "S2_2") (pintype "passive"))
      (node (ref "Q13,16") (pin "5") (pinfunction "S1_5") (pintype "passive"))
      (node (ref "Q14,15") (pin "5") (pinfunction "Sn_5") (pintype "passive"))
      (node (ref "Q17,18") (pin "5") (pinfunction "Sn_5") (pintype "passive"))
      (node (ref "Q19,22") (pin "2") (pinfunction "S2_2") (pintype "passive"))
      (node (ref "Q19,22") (pin "5") (pinfunction "S1_5") (pintype "passive"))
      (node (ref "Q2,3") (pin "5") (pinfunction "Sn_5") (pintype "passive"))
      (node (ref "Q20,21") (pin "5") (pinfunction "Sn_5") (pintype "passive"))
      (node (ref "Q23,24") (pin "5") (pinfunction "Sn_5") (pintype "passive"))
      (node (ref "Q25,28") (pin "2") (pinfunction "S2_2") (pintype "passive"))
      (node (ref "Q25,28") (pin "5") (pinfunction "S1_5") (pintype "passive"))
      (node (ref "Q26,27") (pin "5") (pinfunction "Sn_5") (pintype "passive"))
      (node (ref "Q29,30") (pin "5") (pinfunction "Sn_5") (pintype "passive"))
      (node (ref "Q31,34") (pin "2") (pinfunction "S2_2") (pintype "passive"))
      (node (ref "Q31,34") (pin "5") (pinfunction "S1_5") (pintype "passive"))
      (node (ref "Q32,33") (pin "5") (pinfunction "Sn_5") (pintype "passive"))
      (node (ref "Q35,36") (pin "5") (pinfunction "Sn_5") (pintype "passive"))
      (node (ref "Q5,6") (pin "5") (pinfunction "Sn_5") (pintype "passive"))
      (node (ref "Q7,10") (pin "2") (pinfunction "S2_2") (pintype "passive"))
      (node (ref "Q7,10") (pin "5") (pinfunction "S1_5") (pintype "passive"))
      (node (ref "Q8,9") (pin "5") (pinfunction "Sn_5") (pintype "passive"))
      (node (ref "U101") (pin "3") (pinfunction "Vee_3") (pintype "passive"))
      (node (ref "U101") (pin "9") (pinfunction "GND_9") (pintype "passive"))
      (node (ref "U102") (pin "3") (pinfunction "Vee_3") (pintype "passive"))
      (node (ref "U102") (pin "9") (pinfunction "GND_9") (pintype "passive"))
      (node (ref "U103") (pin "3") (pinfunction "Vee_3") (pintype "passive"))
      (node (ref "U103") (pin "9") (pinfunction "GND_9") (pintype "passive"))
      (node (ref "U104") (pin "3") (pinfunction "Vee_3") (pintype "passive"))
      (node (ref "U104") (pin "9") (pinfunction "GND_9") (pintype "passive"))
      (node (ref "U105") (pin "3") (pinfunction "Vee_3") (pintype "passive"))
      (node (ref "U105") (pin "9") (pinfunction "GND_9") (pintype "passive"))
      (node (ref "U106") (pin "3") (pinfunction "Vee_3") (pintype "passive"))
      (node (ref "U106") (pin "9") (pinfunction "GND_9") (pintype "passive"))
      (node (ref "Z101") (pin "A") (pintype "passive"))
      (node (ref "Z102") (pin "A") (pintype "passive"))
      (node (ref "Z103") (pin "A") (pintype "passive"))
      (node (ref "Z104") (pin "A") (pintype "passive"))
      (node (ref "Z105") (pin "A") (pintype "passive"))
      (node (ref "Z106") (pin "A") (pintype "passive"))
    )
    (net (code "46") (name "Net-(Q1,4-D1)") (class "Default")
      (node (ref "Q1,4") (pin "6") (pinfunction "D1_6") (pintype "passive"))
      (node (ref "R102") (pin "1") (pinfunction "1_1") (pintype "passive"))
    )
    (net (code "47") (name "Net-(Q1,4-D2)") (class "Default")
      (node (ref "Q1,4") (pin "4") (pinfunction "D2_4") (pintype "passive"))
      (node (ref "R104") (pin "1") (pinfunction "1_1") (pintype "passive"))
    )
    (net (code "48") (name "Net-(Q2,3-Dn)") (class "Default")
      (node (ref "M1") (pin "2") (pinfunction "2_2") (pintype "passive"))
      (node (ref "Q2,3") (pin "4") (pinfunction "Dp_4") (pintype "passive"))
      (node (ref "Q2,3") (pin "6") (pinfunction "Dn_6") (pintype "passive"))
      (node (ref "R173") (pin "2") (pinfunction "2_2") (pintype "passive"))
    )
    (net (code "49") (name "Net-(Q2,3-Gp)") (class "Default")
      (node (ref "Q2,3") (pin "3") (pinfunction "Gp_3") (pintype "passive"))
      (node (ref "R101") (pin "1") (pinfunction "1_1") (pintype "passive"))
      (node (ref "R102") (pin "2") (pinfunction "2_2") (pintype "passive"))
    )
    (net (code "50") (name "Net-(Q5,6-Dn)") (class "Default")
      (node (ref "M1") (pin "1") (pinfunction "1_1") (pintype "passive"))
      (node (ref "Q5,6") (pin "4") (pinfunction "Dp_4") (pintype "passive"))
      (node (ref "Q5,6") (pin "6") (pinfunction "Dn_6") (pintype "passive"))
    )
    (net (code "51") (name "Net-(Q5,6-Gp)") (class "Default")
      (node (ref "Q5,6") (pin "3") (pinfunction "Gp_3") (pintype "passive"))
      (node (ref "R103") (pin "1") (pinfunction "1_1") (pintype "passive"))
      (node (ref "R104") (pin "2") (pinfunction "2_2") (pintype "passive"))
    )
    (net (code "52") (name "Net-(Q7,10-D1)") (class "Default")
      (node (ref "Q7,10") (pin "6") (pinfunction "D1_6") (pintype "passive"))
      (node (ref "R108") (pin "1") (pinfunction "1_1") (pintype "passive"))
    )
    (net (code "53") (name "Net-(Q7,10-D2)") (class "Default")
      (node (ref "Q7,10") (pin "4") (pinfunction "D2_4") (pintype "passive"))
      (node (ref "R110") (pin "1") (pinfunction "1_1") (pintype "passive"))
    )
    (net (code "54") (name "Net-(Q8,9-Dn)") (class "Default")
      (node (ref "M2") (pin "2") (pinfunction "2_2") (pintype "passive"))
      (node (ref "Q8,9") (pin "4") (pinfunction "Dp_4") (pintype "passive"))
      (node (ref "Q8,9") (pin "6") (pinfunction "Dn_6") (pintype "passive"))
      (node (ref "R174") (pin "2") (pinfunction "2_2") (pintype "passive"))
    )
    (net (code "55") (name "Net-(Q8,9-Gp)") (class "Default")
      (node (ref "Q8,9") (pin "3") (pinfunction "Gp_3") (pintype "passive"))
      (node (ref "R107") (pin "1") (pinfunction "1_1") (pintype "passive"))
      (node (ref "R108") (pin "2") (pinfunction "2_2") (pintype "passive"))
    )
    (net (code "56") (name "Net-(Q11,12-Dn)") (class "Default")
      (node (ref "M2") (pin "1") (pinfunction "1_1") (pintype "passive"))
      (node (ref "Q11,12") (pin "4") (pinfunction "Dp_4") (pintype "passive"))
      (node (ref "Q11,12") (pin "6") (pinfunction "Dn_6") (pintype "passive"))
    )
    (net (code "57") (name "Net-(Q11,12-Gp)") (class "Default")
      (node (ref "Q11,12") (pin "3") (pinfunction "Gp_3") (pintype "passive"))
      (node (ref "R109") (pin "1") (pinfunction "1_1") (pintype "passive"))
      (node (ref "R110") (pin "2") (pinfunction "2_2") (pintype "passive"))
    )
    (net (code "58") (name "Net-(Q13,16-D1)") (class "Default")
      (node (ref "Q13,16") (pin "6") (pinfunction "D1_6") (pintype "passive"))
      (node (ref "R114") (pin "1") (pinfunction "1_1") (pintype "passive"))
    )
    (net (code "59") (name "Net-(Q13,16-D2)") (class "Default")
      (node (ref "Q13,16") (pin "4") (pinfunction "D2_4") (pintype "passive"))
      (node (ref "R116") (pin "1") (pinfunction "1_1") (pintype "passive"))
    )
    (net (code "60") (name "Net-(Q14,15-Dn)") (class "Default")
      (node (ref "M3") (pin "2") (pinfunction "2_2") (pintype "passive"))
      (node (ref "Q14,15") (pin "4") (pinfunction "Dp_4") (pintype "passive"))
      (node (ref "Q14,15") (pin "6") (pinfunction "Dn_6") (pintype "passive"))
      (node (ref "R175") (pin "2") (pinfunction "2_2") (pintype "passive"))
    )
    (net (code "61") (name "Net-(Q14,15-Gp)") (class "Default")
      (node (ref "Q14,15") (pin "3") (pinfunction "Gp_3") (pintype "passive"))
      (node (ref "R113") (pin "1") (pinfunction "1_1") (pintype "passive"))
      (node (ref "R114") (pin "2") (pinfunction "2_2") (pintype "passive"))
    )
    (net (code "62") (name "Net-(Q17,18-Dn)") (class "Default")
      (node (ref "M3") (pin "1") (pinfunction "1_1") (pintype "passive"))
      (node (ref "Q17,18") (pin "4") (pinfunction "Dp_4") (pintype "passive"))
      (node (ref "Q17,18") (pin "6") (pinfunction "Dn_6") (pintype "passive"))
    )
    (net (code "63") (name "Net-(Q17,18-Gp)") (class "Default")
      (node (ref "Q17,18") (pin "3") (pinfunction "Gp_3") (pintype "passive"))
      (node (ref "R115") (pin "1") (pinfunction "1_1") (pintype "passive"))
      (node (ref "R116") (pin "2") (pinfunction "2_2") (pintype "passive"))
    )
    (net (code "64") (name "Net-(Q19,22-D1)") (class "Default")
      (node (ref "Q19,22") (pin "6") (pinfunction "D1_6") (pintype "passive"))
      (node (ref "R120") (pin "1") (pinfunction "1_1") (pintype "passive"))
    )
    (net (code "65") (name "Net-(Q19,22-D2)") (class "Default")
      (node (ref "Q19,22") (pin "4") (pinfunction "D2_4") (pintype "passive"))
      (node (ref "R122") (pin "1") (pinfunction "1_1") (pintype "passive"))
    )
    (net (code "66") (name "Net-(Q20,21-Dn)") (class "Default")
      (node (ref "M4") (pin "2") (pinfunction "2_2") (pintype "passive"))
      (node (ref "Q20,21") (pin "4") (pinfunction "Dp_4") (pintype "passive"))
      (node (ref "Q20,21") (pin "6") (pinfunction "Dn_6") (pintype "passive"))
      (node (ref "R176") (pin "2") (pinfunction "2_2") (pintype "passive"))
    )
    (net (code "67") (name "Net-(Q20,21-Gp)") (class "Default")
      (node (ref "Q20,21") (pin "3") (pinfunction "Gp_3") (pintype "passive"))
      (node (ref "R119") (pin "1") (pinfunction "1_1") (pintype "passive"))
      (node (ref "R120") (pin "2") (pinfunction "2_2") (pintype "passive"))
    )
    (net (code "68") (name "Net-(Q23,24-Dn)") (class "Default")
      (node (ref "M4") (pin "1") (pinfunction "1_1") (pintype "passive"))
      (node (ref "Q23,24") (pin "4") (pinfunction "Dp_4") (pintype "passive"))
      (node (ref "Q23,24") (pin "6") (pinfunction "Dn_6") (pintype "passive"))
    )
    (net (code "69") (name "Net-(Q23,24-Gp)") (class "Default")
      (node (ref "Q23,24") (pin "3") (pinfunction "Gp_3") (pintype "passive"))
      (node (ref "R121") (pin "1") (pinfunction "1_1") (pintype "passive"))
      (node (ref "R122") (pin "2") (pinfunction "2_2") (pintype "passive"))
    )
    (net (code "70") (name "Net-(Q25,28-D1)") (class "Default")
      (node (ref "Q25,28") (pin "6") (pinfunction "D1_6") (pintype "passive"))
      (node (ref "R126") (pin "1") (pinfunction "1_1") (pintype "passive"))
    )
    (net (code "71") (name "Net-(Q25,28-D2)") (class "Default")
      (node (ref "Q25,28") (pin "4") (pinfunction "D2_4") (pintype "passive"))
      (node (ref "R128") (pin "1") (pinfunction "1_1") (pintype "passive"))
    )
    (net (code "72") (name "Net-(Q26,27-Dn)") (class "Default")
      (node (ref "M5") (pin "2") (pinfunction "2_2") (pintype "passive"))
      (node (ref "Q26,27") (pin "4") (pinfunction "Dp_4") (pintype "passive"))
      (node (ref "Q26,27") (pin "6") (pinfunction "Dn_6") (pintype "passive"))
      (node (ref "R177") (pin "2") (pinfunction "2_2") (pintype "passive"))
    )
    (net (code "73") (name "Net-(Q26,27-Gp)") (class "Default")
      (node (ref "Q26,27") (pin "3") (pinfunction "Gp_3") (pintype "passive"))
      (node (ref "R125") (pin "1") (pinfunction "1_1") (pintype "passive"))
      (node (ref "R126") (pin "2") (pinfunction "2_2") (pintype "passive"))
    )
    (net (code "74") (name "Net-(Q29,30-Dn)") (class "Default")
      (node (ref "M5") (pin "1") (pinfunction "1_1") (pintype "passive"))
      (node (ref "Q29,30") (pin "4") (pinfunction "Dp_4") (pintype "passive"))
      (node (ref "Q29,30") (pin "6") (pinfunction "Dn_6") (pintype "passive"))
    )
    (net (code "75") (name "Net-(Q29,30-Gp)") (class "Default")
      (node (ref "Q29,30") (pin "3") (pinfunction "Gp_3") (pintype "passive"))
      (node (ref "R127") (pin "1") (pinfunction "1_1") (pintype "passive"))
      (node (ref "R128") (pin "2") (pinfunction "2_2") (pintype "passive"))
    )
    (net (code "76") (name "Net-(Q31,34-D1)") (class "Default")
      (node (ref "Q31,34") (pin "6") (pinfunction "D1_6") (pintype "passive"))
      (node (ref "R132") (pin "1") (pinfunction "1_1") (pintype "passive"))
    )
    (net (code "77") (name "Net-(Q31,34-D2)") (class "Default")
      (node (ref "Q31,34") (pin "4") (pinfunction "D2_4") (pintype "passive"))
      (node (ref "R134") (pin "1") (pinfunction "1_1") (pintype "passive"))
    )
    (net (code "78") (name "Net-(Q32,33-Dn)") (class "Default")
      (node (ref "M6") (pin "2") (pinfunction "2_2") (pintype "passive"))
      (node (ref "Q32,33") (pin "4") (pinfunction "Dp_4") (pintype "passive"))
      (node (ref "Q32,33") (pin "6") (pinfunction "Dn_6") (pintype "passive"))
      (node (ref "R178") (pin "2") (pinfunction "2_2") (pintype "passive"))
    )
    (net (code "79") (name "Net-(Q32,33-Gp)") (class "Default")
      (node (ref "Q32,33") (pin "3") (pinfunction "Gp_3") (pintype "passive"))
      (node (ref "R131") (pin "1") (pinfunction "1_1") (pintype "passive"))
      (node (ref "R132") (pin "2") (pinfunction "2_2") (pintype "passive"))
    )
    (net (code "80") (name "Net-(Q35,36-Dn)") (class "Default")
      (node (ref "M6") (pin "1") (pinfunction "1_1") (pintype "passive"))
      (node (ref "Q35,36") (pin "4") (pinfunction "Dp_4") (pintype "passive"))
      (node (ref "Q35,36") (pin "6") (pinfunction "Dn_6") (pintype "passive"))
    )
    (net (code "81") (name "Net-(Q35,36-Gp)") (class "Default")
      (node (ref "Q35,36") (pin "3") (pinfunction "Gp_3") (pintype "passive"))
      (node (ref "R133") (pin "1") (pinfunction "1_1") (pintype "passive"))
      (node (ref "R134") (pin "2") (pinfunction "2_2") (pintype "passive"))
    )
    (net (code "82") (name "Net-(U101-OUT_A)") (class "Default")
      (node (ref "R105") (pin "2") (pinfunction "2_2") (pintype "passive"))
      (node (ref "U101") (pin "7") (pinfunction "OUT_A_7") (pintype "passive"))
    )
    (net (code "83") (name "Net-(U101-OUT_B)") (class "Default")
      (node (ref "R106") (pin "2") (pinfunction "2_2") (pintype "passive"))
      (node (ref "U101") (pin "5") (pinfunction "OUT_B_5") (pintype "passive"))
    )
    (net (code "84") (name "Net-(U102-OUT_A)") (class "Default")
      (node (ref "R111") (pin "2") (pinfunction "2_2") (pintype "passive"))
      (node (ref "U102") (pin "7") (pinfunction "OUT_A_7") (pintype "passive"))
    )
    (net (code "85") (name "Net-(U102-OUT_B)") (class "Default")
      (node (ref "R112") (pin "2") (pinfunction "2_2") (pintype "passive"))
      (node (ref "U102") (pin "5") (pinfunction "OUT_B_5") (pintype "passive"))
    )
    (net (code "86") (name "Net-(U103-OUT_A)") (class "Default")
      (node (ref "R117") (pin "2") (pinfunction "2_2") (pintype "passive"))
      (node (ref "U103") (pin "7") (pinfunction "OUT_A_7") (pintype "passive"))
    )
    (net (code "87") (name "Net-(U103-OUT_B)") (class "Default")
      (node (ref "R118") (pin "2") (pinfunction "2_2") (pintype "passive"))
      (node (ref "U103") (pin "5") (pinfunction "OUT_B_5") (pintype "passive"))
    )
    (net (code "88") (name "Net-(U104-OUT_A)") (class "Default")
      (node (ref "R123") (pin "2") (pinfunction "2_2") (pintype "passive"))
      (node (ref "U104") (pin "7") (pinfunction "OUT_A_7") (pintype "passive"))
    )
    (net (code "89") (name "Net-(U104-OUT_B)") (class "Default")
      (node (ref "R124") (pin "2") (pinfunction "2_2") (pintype "passive"))
      (node (ref "U104") (pin "5") (pinfunction "OUT_B_5") (pintype "passive"))
    )
    (net (code "90") (name "Net-(U105-OUT_A)") (class "Default")
      (node (ref "R129") (pin "2") (pinfunction "2_2") (pintype "passive"))
      (node (ref "U105") (pin "7") (pinfunction "OUT_A_7") (pintype "passive"))
    )
    (net (code "91") (name "Net-(U105-OUT_B)") (class "Default")
      (node (ref "R130") (pin "2") (pinfunction "2_2") (pintype "passive"))
      (node (ref "U105") (pin "5") (pinfunction "OUT_B_5") (pintype "passive"))
    )
    (net (code "92") (name "Net-(U106-OUT_A)") (class "Default")
      (node (ref "R135") (pin "2") (pinfunction "2_2") (pintype "passive"))
      (node (ref "U106") (pin "7") (pinfunction "OUT_A_7") (pintype "passive"))
    )
    (net (code "93") (name "Net-(U106-OUT_B)") (class "Default")
      (node (ref "R136") (pin "2") (pinfunction "2_2") (pintype "passive"))
      (node (ref "U106") (pin "5") (pinfunction "OUT_B_5") (pintype "passive"))
    )
    (net (code "94") (name "unconnected-(M7-Pad1)") (class "Default")
      (node (ref "M7") (pin "1") (pinfunction "1_1") (pintype "passive"))
    )
    (net (code "95") (name "unconnected-(M7-Pad2)") (class "Default")
      (node (ref "M7") (pin "2") (pinfunction "2_2") (pintype "passive"))
    )
    (net (code "96") (name "unconnected-(M8-Pad1)") (class "Default")
      (node (ref "M8") (pin "1") (pinfunction "1_1") (pintype "passive"))
    )
    (net (code "97") (name "unconnected-(M8-Pad2)") (class "Default")
      (node (ref "M8") (pin "2") (pinfunction "2_2") (pintype "passive"))
    )
    (net (code "98") (name "unconnected-(M9-Pad1)") (class "Default")
      (node (ref "M9") (pin "1") (pinfunction "1_1") (pintype "passive"))
    )
    (net (code "99") (name "unconnected-(M9-Pad2)") (class "Default")
      (node (ref "M9") (pin "2") (pinfunction "2_2") (pintype "passive"))
    )
    (net (code "100") (name "unconnected-(M10-Pad1)") (class "Default")
      (node (ref "M10") (pin "1") (pinfunction "1_1") (pintype "passive"))
    )
    (net (code "101") (name "unconnected-(M10-Pad2)") (class "Default")
      (node (ref "M10") (pin "2") (pinfunction "2_2") (pintype "passive"))
    )
    (net (code "102") (name "unconnected-(M11-Pad1)") (class "Default")
      (node (ref "M11") (pin "1") (pinfunction "1_1") (pintype "passive"))
    )
    (net (code "103") (name "unconnected-(M11-Pad2)") (class "Default")
      (node (ref "M11") (pin "2") (pinfunction "2_2") (pintype "passive"))
    )
    (net (code "104") (name "unconnected-(M12-Pad1)") (class "Default")
      (node (ref "M12") (pin "1") (pinfunction "1_1") (pintype "passive"))
    )
    (net (code "105") (name "unconnected-(M12-Pad2)") (class "Default")
      (node (ref "M12") (pin "2") (pinfunction "2_2") (pintype "passive"))
    )
    (net (code "106") (name "unconnected-(U101-NC-Pad1)") (class "Default")
      (node (ref "U101") (pin "1") (pinfunction "NC_1") (pintype "passive+no_connect"))
    )
    (net (code "107") (name "unconnected-(U101-NC-Pad8)") (class "Default")
      (node (ref "U101") (pin "8") (pinfunction "NC_8") (pintype "passive+no_connect"))
    )
    (net (code "108") (name "unconnected-(U102-NC-Pad1)") (class "Default")
      (node (ref "U102") (pin "1") (pinfunction "NC_1") (pintype "passive+no_connect"))
    )
    (net (code "109") (name "unconnected-(U102-NC-Pad8)") (class "Default")
      (node (ref "U102") (pin "8") (pinfunction "NC_8") (pintype "passive+no_connect"))
    )
    (net (code "110") (name "unconnected-(U103-NC-Pad1)") (class "Default")
      (node (ref "U103") (pin "1") (pinfunction "NC_1") (pintype "passive+no_connect"))
    )
    (net (code "111") (name "unconnected-(U103-NC-Pad8)") (class "Default")
      (node (ref "U103") (pin "8") (pinfunction "NC_8") (pintype "passive+no_connect"))
    )
    (net (code "112") (name "unconnected-(U104-NC-Pad1)") (class "Default")
      (node (ref "U104") (pin "1") (pinfunction "NC_1") (pintype "passive+no_connect"))
    )
    (net (code "113") (name "unconnected-(U104-NC-Pad8)") (class "Default")
      (node (ref "U104") (pin "8") (pinfunction "NC_8") (pintype "passive+no_connect"))
    )
    (net (code "114") (name "unconnected-(U105-NC-Pad1)") (class "Default")
      (node (ref "U105") (pin "1") (pinfunction "NC_1") (pintype "passive+no_connect"))
    )
    (net (code "115") (name "unconnected-(U105-NC-Pad8)") (class "Default")
      (node (ref "U105") (pin "8") (pinfunction "NC_8") (pintype "passive+no_connect"))
    )
    (net (code "116") (name "unconnected-(U106-NC-Pad1)") (class "Default")
      (node (ref "U106") (pin "1") (pinfunction "NC_1") (pintype "passive+no_connect"))
    )
    (net (code "117") (name "unconnected-(U106-NC-Pad8)") (class "Default")
      (node (ref "U106") (pin "8") (pinfunction "NC_8") (pintype "passive+no_connect"))
    )
  )
)
